# ESC_Tester_SCH.net
KiCad netlist of a schematic drawn in Altium Designer
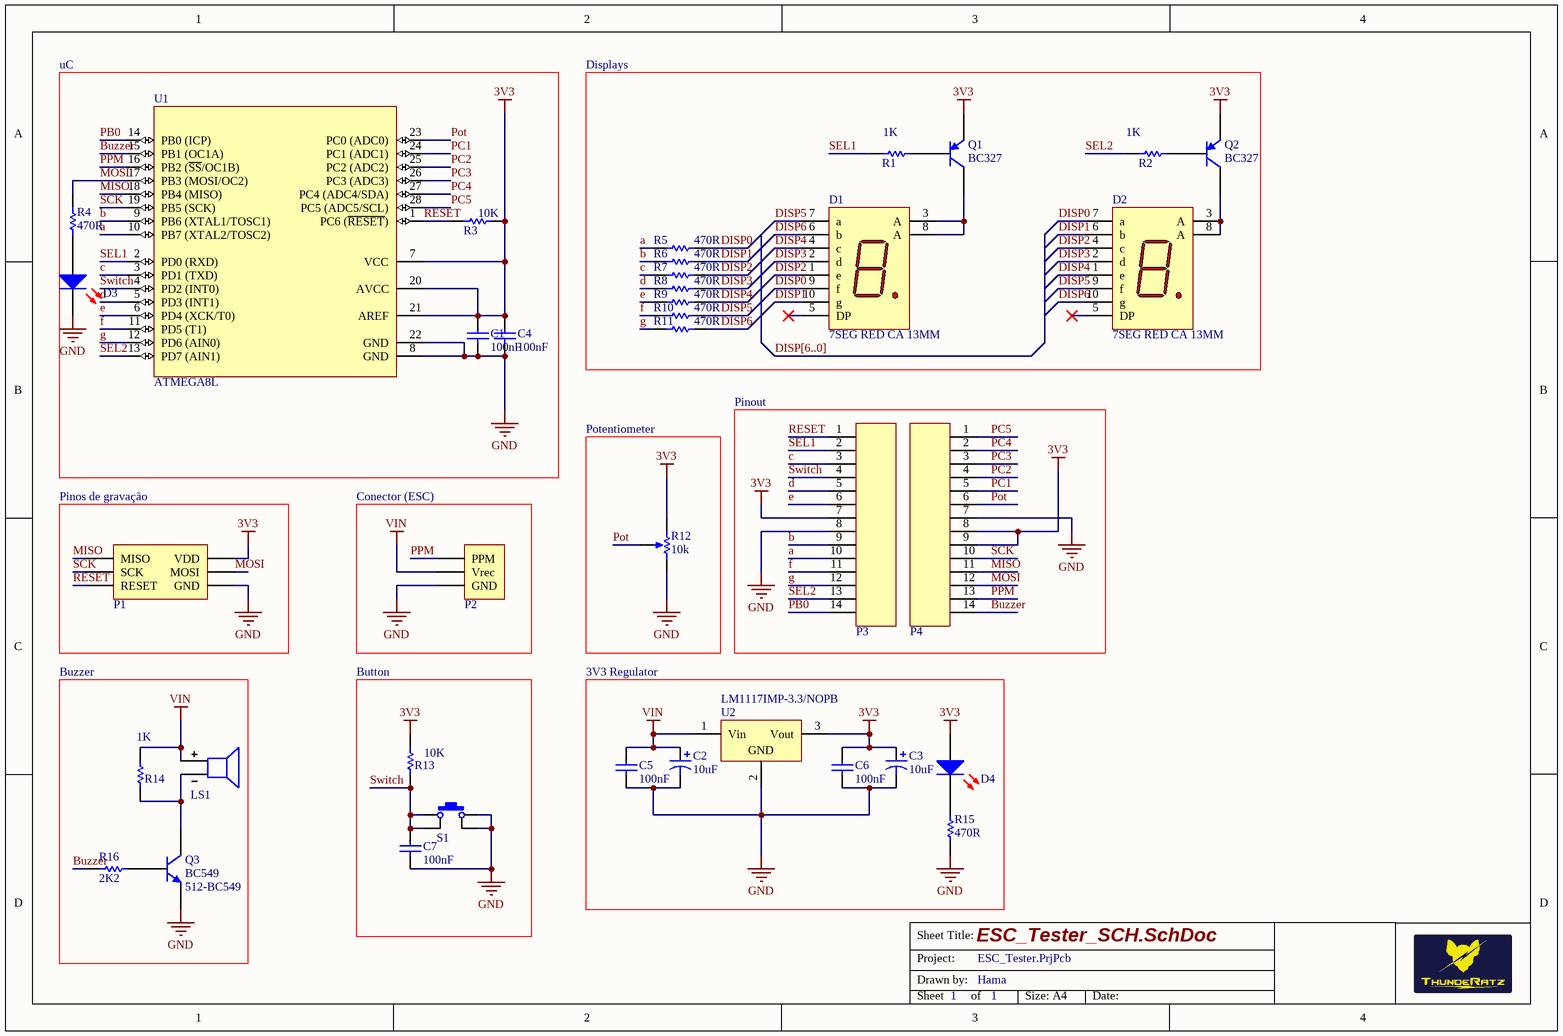
[diagram p0: ESC_Tester_SCH.SchDoc]

(export (version "E")
  (design (tool "Eeschema 10.0.6"))
  (components
    (comp (ref "C1")
      (value "Cap Film 0.1uF")
      (footprint "Cap Film 0.1uF")
      (description "Cap Film 0.1uF 63V PET 10% (7.2 X 2.5 X 6.5mm) Radial 5mm 125C Bulk")
      (fields
        (field (name "MANUFACTURER") "TDK EPCOS")
        (field (name "MANUFACTURER PART NUMBER") "B32529C104K")
        (field (name "CAPACITANCE") "100nF")
      )
      (libsource (lib "ESC_Tester_SCHLIB") (part "Cap Film 0.1uF - B32529C104K"))
    )
    (comp (ref "C2")
      (value "10uF")
      (footprint "CAP RAD 10UF 35V")
      (description "CAP ELE RAD 10uF 16V")
      (fields (field (name "MANUFACTURER PART NUMBER") "IMP1295"))
      (libsource (lib "ESC_Tester_SCHLIB") (part "CAP ELE RAD 10uF 16V"))
    )
    (comp (ref "C3")
      (value "10uF")
      (footprint "CAP RAD 10UF 35V")
      (description "CAP ELE RAD 10uF 16V")
      (fields (field (name "MANUFACTURER PART NUMBER") "IMP1295"))
      (libsource (lib "ESC_Tester_SCHLIB") (part "CAP ELE RAD 10uF 16V"))
    )
    (comp (ref "C4")
      (value "Cap Film 0.1uF")
      (footprint "Cap Film 0.1uF")
      (description "Cap Film 0.1uF 63V PET 10% (7.2 X 2.5 X 6.5mm) Radial 5mm 125C Bulk")
      (fields
        (field (name "MANUFACTURER") "TDK EPCOS")
        (field (name "MANUFACTURER PART NUMBER") "B32529C104K")
        (field (name "CAPACITANCE") "100nF")
      )
      (libsource (lib "ESC_Tester_SCHLIB") (part "Cap Film 0.1uF - B32529C104K"))
    )
    (comp (ref "C5")
      (value "Cap Film 0.1uF")
      (footprint "Cap Film 0.1uF")
      (description "Cap Film 0.1uF 63V PET 10% (7.2 X 2.5 X 6.5mm) Radial 5mm 125C Bulk")
      (fields
        (field (name "MANUFACTURER") "TDK EPCOS")
        (field (name "MANUFACTURER PART NUMBER") "B32529C104K")
        (field (name "CAPACITANCE") "100nF")
      )
      (libsource (lib "ESC_Tester_SCHLIB") (part "Cap Film 0.1uF - B32529C104K"))
    )
    (comp (ref "C6")
      (value "Cap Film 0.1uF")
      (footprint "Cap Film 0.1uF")
      (description "Cap Film 0.1uF 63V PET 10% (7.2 X 2.5 X 6.5mm) Radial 5mm 125C Bulk")
      (fields
        (field (name "MANUFACTURER") "TDK EPCOS")
        (field (name "MANUFACTURER PART NUMBER") "B32529C104K")
        (field (name "CAPACITANCE") "100nF")
      )
      (libsource (lib "ESC_Tester_SCHLIB") (part "Cap Film 0.1uF - B32529C104K"))
    )
    (comp (ref "C7")
      (value "Cap Film 0.1uF")
      (footprint "Cap Film 0.1uF")
      (description "Cap Film 0.1uF 63V PET 10% (7.2 X 2.5 X 6.5mm) Radial 5mm 125C Bulk")
      (fields
        (field (name "MANUFACTURER") "TDK EPCOS")
        (field (name "MANUFACTURER PART NUMBER") "B32529C104K")
        (field (name "CAPACITANCE") "100nF")
      )
      (libsource (lib "ESC_Tester_SCHLIB") (part "Cap Film 0.1uF - B32529C104K"))
    )
    (comp (ref "D1")
      (value "7SEG RED CA 13MM")
      (footprint "7SEG RED PTH")
      (description "PHOTONIC - PHDE113A - DISPLAY, SEVEN SEGMENT, 13MM, RED")
      (fields (field (name "MANUFACTURER") "Photonic") (field (name "MANUFACTURER PART NUMBER") "PHDE113A"))
      (libsource (lib "PS_LIB_SCH") (part "7SEG RED CA 13MM"))
    )
    (comp (ref "D2")
      (value "7SEG RED CA 13MM")
      (footprint "7SEG RED PTH")
      (description "PHOTONIC - PHDE113A - DISPLAY, SEVEN SEGMENT, 13MM, RED")
      (fields (field (name "MANUFACTURER") "Photonic") (field (name "MANUFACTURER PART NUMBER") "PHDE113A"))
      (libsource (lib "PS_LIB_SCH") (part "7SEG RED CA 13MM"))
    )
    (comp (ref "D3")
      (value "LED 5MM RED")
      (footprint "LED 5MM RED")
      (fields (field (name "MANUFACTURER") "Paralight") (field (name "MANUFACTURER PART NUMBER") "IMP585"))
      (libsource (lib "ESC_Tester_SCHLIB") (part "LED 5MM RED"))
    )
    (comp (ref "D4")
      (value "LED 5MM RED")
      (footprint "LED 5MM RED")
      (fields (field (name "MANUFACTURER") "Paralight") (field (name "MANUFACTURER PART NUMBER") "IMP585"))
      (libsource (lib "ESC_Tester_SCHLIB") (part "LED 5MM RED"))
    )
    (comp (ref "LS1")
      (value "Buzzer")
      (footprint "BUZZER 12x6MM")
      (description "AUDIO PIEZO TRANSDUCER 30V TH")
      (fields
        (field (name "MANUFACTURER") "TDK Corporation")
        (field (name "MANUFACTURER PART NUMBER") "PS1240P02BT")
      )
      (libsource (lib "ESC_Tester_SCHLIB") (part "AUDIO PIEZO TRANSDUCER 30V TH"))
    )
    (comp (ref "P1")
      (value "87758-4016")
      (footprint "HDR MALE 2x3")
      (description "Headers & Wire Housings VERT HEADER 40P Lead Free")
      (fields (field (name "MANUFACTURER") "Molex"))
      (libsource (lib "ESC_Tester_SCHLIB") (part "87758-4016"))
    )
    (comp (ref "P2")
      (value "920-0018-01")
      (footprint "HDR MALE 1x3")
      (description "Headers & Wire Housings 40Pin 2mm Spacing Single Row Hdrs, 5pc")
      (fields (field (name "MANUFACTURER") "SchmartBoard"))
      (libsource (lib "PS_LIB_SCH") (part "920-0018-01_1"))
    )
    (comp (ref "P3")
      (value "Header Female 1x14")
      (footprint "HDR FEMALE 1x14")
      (description "Headers & Wire Housings 40Pin 2mm Spacing Single Row Hdrs, 5pc")
      (fields (field (name "MANUFACTURER") "Cromax"))
      (libsource (lib "ESC_Tester_SCHLIB") (part "Header Female 1x14"))
    )
    (comp (ref "P4")
      (value "Header Female 1x14")
      (footprint "HDR FEMALE 1x14")
      (description "Headers & Wire Housings 40Pin 2mm Spacing Single Row Hdrs, 5pc")
      (fields (field (name "MANUFACTURER") "Cromax"))
      (libsource (lib "") (part "Header Female 1x14_1"))
    )
    (comp (ref "Q1")
      (value "BC327")
      (footprint "TO92")
      (description "Bipolar Transistors - BJT PNP -45V -800mA HFE/630")
      (fields (field (name "MANUFACTURER") "Fairchild Semiconductor"))
      (libsource (lib "PS_LIB_SCH") (part "BC327 BJT PNP TO92"))
    )
    (comp (ref "Q2")
      (value "BC327")
      (footprint "TO92")
      (description "Bipolar Transistors - BJT PNP -45V -800mA HFE/630")
      (fields (field (name "MANUFACTURER") "Fairchild Semiconductor"))
      (libsource (lib "PS_LIB_SCH") (part "BC327 BJT PNP TO92"))
    )
    (comp (ref "Q3")
      (value "BC549")
      (footprint "TO92")
      (description "TRANS NPN 30V 0.1A TO-92")
      (fields
        (field (name "MANUFACTURER") "Fairchild Semiconductor")
        (field (name "SUPPLIER PART NUMBER 1") "512-BC549")
      )
      (libsource (lib "PS_LIB_SCH") (part "BC549"))
    )
    (comp (ref "R1")
      (value "RES 1K 1/4W CARBON FILM")
      (footprint "RES 1K 1/4W CARBON FILM")
      (description "RES 1K OHM 1/4W 5% CARBON FILM")
      (fields
        (field (name "MANUFACTURER") "Ty-Ohm")
        (field (name "MANUFACTURER PART NUMBER") "CR25")
        (field (name "RESISTANCE (OHMS)") "1K")
      )
      (libsource (lib "PS_LIB_SCH") (part "RES 1K 1/4W CARBON FILM"))
    )
    (comp (ref "R2")
      (value "RES 1K 1/4W CARBON FILM")
      (footprint "RES 1K 1/4W CARBON FILM")
      (description "RES 1K OHM 1/4W 5% CARBON FILM")
      (fields
        (field (name "MANUFACTURER") "Ty-Ohm")
        (field (name "MANUFACTURER PART NUMBER") "CR25")
        (field (name "RESISTANCE (OHMS)") "1K")
      )
      (libsource (lib "PS_LIB_SCH") (part "RES 1K 1/4W CARBON FILM"))
    )
    (comp (ref "R3")
      (value "RES 10K 1/4W CARBON FILM")
      (footprint "RES 10K 1/4W CARBON FILM")
      (description "RES 10K OHM 1/4W 5% CARBON FILM")
      (fields
        (field (name "MANUFACTURER") "Ty-Ohm")
        (field (name "MANUFACTURER PART NUMBER") "CR25")
        (field (name "RESISTANCE (OHMS)") "10K")
      )
      (libsource (lib "ESC_Tester_SCHLIB") (part "RES 10K 1/4W CARBON FILM"))
    )
    (comp (ref "R4")
      (value "RES 470R 1/4W CARBON FILM")
      (footprint "RES 470R 1/4W CARBON FILM_STAND")
      (description "RES 470R OHM 1/4W 5% CARBON FILM")
      (fields
        (field (name "MANUFACTURER") "Ty-Ohm")
        (field (name "MANUFACTURER PART NUMBER") "CR25")
        (field (name "RESISTANCE (OHMS)") "470R")
      )
      (libsource (lib "ESC_Tester_SCHLIB") (part "RES 470R 1/4W CARBON FILM"))
    )
    (comp (ref "R5")
      (value "RES 470R 1/4W CARBON FILM")
      (footprint "RES 470R 1/4W CARBON FILM")
      (description "RES 470R OHM 1/4W 5% CARBON FILM")
      (fields
        (field (name "MANUFACTURER") "Ty-Ohm")
        (field (name "MANUFACTURER PART NUMBER") "CR25")
        (field (name "RESISTANCE (OHMS)") "470R")
      )
      (libsource (lib "PS_LIB_SCH") (part "RES 470R 1/4W CARBON FILM"))
    )
    (comp (ref "R6")
      (value "RES 470R 1/4W CARBON FILM")
      (footprint "RES 470R 1/4W CARBON FILM")
      (description "RES 470R OHM 1/4W 5% CARBON FILM")
      (fields
        (field (name "MANUFACTURER") "Ty-Ohm")
        (field (name "MANUFACTURER PART NUMBER") "CR25")
        (field (name "RESISTANCE (OHMS)") "470R")
      )
      (libsource (lib "PS_LIB_SCH") (part "RES 470R 1/4W CARBON FILM"))
    )
    (comp (ref "R7")
      (value "RES 470R 1/4W CARBON FILM")
      (footprint "RES 470R 1/4W CARBON FILM")
      (description "RES 470R OHM 1/4W 5% CARBON FILM")
      (fields
        (field (name "MANUFACTURER") "Ty-Ohm")
        (field (name "MANUFACTURER PART NUMBER") "CR25")
        (field (name "RESISTANCE (OHMS)") "470R")
      )
      (libsource (lib "PS_LIB_SCH") (part "RES 470R 1/4W CARBON FILM"))
    )
    (comp (ref "R8")
      (value "RES 470R 1/4W CARBON FILM")
      (footprint "RES 470R 1/4W CARBON FILM")
      (description "RES 470R OHM 1/4W 5% CARBON FILM")
      (fields
        (field (name "MANUFACTURER") "Ty-Ohm")
        (field (name "MANUFACTURER PART NUMBER") "CR25")
        (field (name "RESISTANCE (OHMS)") "470R")
      )
      (libsource (lib "PS_LIB_SCH") (part "RES 470R 1/4W CARBON FILM"))
    )
    (comp (ref "R9")
      (value "RES 470R 1/4W CARBON FILM")
      (footprint "RES 470R 1/4W CARBON FILM")
      (description "RES 470R OHM 1/4W 5% CARBON FILM")
      (fields
        (field (name "MANUFACTURER") "Ty-Ohm")
        (field (name "MANUFACTURER PART NUMBER") "CR25")
        (field (name "RESISTANCE (OHMS)") "470R")
      )
      (libsource (lib "PS_LIB_SCH") (part "RES 470R 1/4W CARBON FILM"))
    )
    (comp (ref "R10")
      (value "RES 470R 1/4W CARBON FILM")
      (footprint "RES 470R 1/4W CARBON FILM")
      (description "RES 470R OHM 1/4W 5% CARBON FILM")
      (fields
        (field (name "MANUFACTURER") "Ty-Ohm")
        (field (name "MANUFACTURER PART NUMBER") "CR25")
        (field (name "RESISTANCE (OHMS)") "470R")
      )
      (libsource (lib "PS_LIB_SCH") (part "RES 470R 1/4W CARBON FILM"))
    )
    (comp (ref "R11")
      (value "RES 470R 1/4W CARBON FILM")
      (footprint "RES 470R 1/4W CARBON FILM")
      (description "RES 470R OHM 1/4W 5% CARBON FILM")
      (fields
        (field (name "MANUFACTURER") "Ty-Ohm")
        (field (name "MANUFACTURER PART NUMBER") "CR25")
        (field (name "RESISTANCE (OHMS)") "470R")
      )
      (libsource (lib "PS_LIB_SCH") (part "RES 470R 1/4W CARBON FILM"))
    )
    (comp (ref "R12")
      (value "Pot 10k")
      (footprint "Pot 10k")
      (description "POT 10K OHM 1/20W PLASTIC LINEAR")
      (fields
        (field (name "MANUFACTURER") "TT Electronics/BI")
        (field (name "MANUFACTURER PART NUMBER") "P120PK-Y25BR10K")
        (field (name "RESISTANCE (OHMS)") "10k")
      )
      (libsource (lib "PS_LIB_SCH") (part "Pot 10k"))
    )
    (comp (ref "R13")
      (value "RES 10K 1/4W CARBON FILM")
      (footprint "RES 10K 1/4W CARBON FILM")
      (description "RES 10K OHM 1/4W 5% CARBON FILM")
      (fields
        (field (name "MANUFACTURER") "Ty-Ohm")
        (field (name "MANUFACTURER PART NUMBER") "CR25")
        (field (name "RESISTANCE (OHMS)") "10K")
      )
      (libsource (lib "PS_LIB_SCH") (part "RES 10K 1/4W CARBON FILM"))
    )
    (comp (ref "R14")
      (value "RES 1K 1/4W CARBON FILM")
      (footprint "RES 1K 1/4W CARBON FILM")
      (description "RES 1K OHM 1/4W 5% CARBON FILM")
      (fields
        (field (name "MANUFACTURER") "Ty-Ohm")
        (field (name "MANUFACTURER PART NUMBER") "CR25")
        (field (name "RESISTANCE (OHMS)") "1K")
      )
      (libsource (lib "PS_LIB_SCH") (part "RES 1K 1/4W CARBON FILM"))
    )
    (comp (ref "R15")
      (value "RES 470R 1/4W CARBON FILM")
      (footprint "RES 470R 1/4W CARBON FILM_STAND")
      (description "RES 470R OHM 1/4W 5% CARBON FILM")
      (fields
        (field (name "MANUFACTURER") "Ty-Ohm")
        (field (name "MANUFACTURER PART NUMBER") "CR25")
        (field (name "RESISTANCE (OHMS)") "470R")
      )
      (libsource (lib "ESC_Tester_SCHLIB") (part "RES 470R 1/4W CARBON FILM"))
    )
    (comp (ref "R16")
      (value "RES 2K2 1/4W CARBON FILM")
      (footprint "RES 2K2 1/4W CARBON FILM")
      (description "RES 2K2 OHM 1/4W 5% CARBON FILM")
      (fields
        (field (name "MANUFACTURER") "Ty-Ohm")
        (field (name "MANUFACTURER PART NUMBER") "CR25")
        (field (name "RESISTANCE (OHMS)") "2K2")
      )
      (libsource (lib "ESC_Tester_SCHLIB") (part "RES 2K2 1/4W CARBON FILM"))
    )
    (comp (ref "S1")
      (value "SPST-NO")
      (footprint "TACT SWITCH 6X6X7MM")
      (description "SWITCH TACTILE SPST-NO 0.02A 15V")
      (fields
        (field (name "MANUFACTURER") "Panasonic Electronic Components")
        (field (name "MANUFACTURER PART NUMBER") "EVQ-PAC07K")
      )
      (libsource (lib "PS_LIB_SCH") (part "SWITCH TACTILE SPST-NO 0.02A 15V"))
    )
    (comp (ref "U1")
      (value "ATMEGA8L")
      (footprint "DIP28")
      (description "8-bit Microcontrollers - MCU 8kB Flash 0.5kB EEPROM 23 I/O Pins")
      (fields (field (name "MANUFACTURER") "Atmel") (field (name "MANUFACTURER PART NUMBER") "ATmega8L-8PU"))
      (libsource (lib "PS_LIB_SCH") (part "MCU ATMEGA8L-8PU PDIP28_1"))
    )
    (comp (ref "U2")
      (value "LM1117IMP-3.3/NOPB")
      (footprint "TO220AB")
      (description "TEXAS INSTRUMENTS   LM1117IMP-3.3/NOPB   LDO, 1.2VDO, 3.3V, 1%, 0.8A, 3SOT223")
      (fields (field (name "MANUFACTURER") "Texas Instruments"))
      (libsource (lib "ESC_Tester_SCHLIB") (part "LM1117IMP-3.3/NOPB"))
    )
  )
  (nets
    (net (code "1") (name "/Buzzer") (class "Default")
      (node (ref "P4") (pin "14") (pintype "passive"))
      (node (ref "R16") (pin "1") (pinfunction "1_1") (pintype "passive"))
      (node (ref "U1") (pin "15") (pinfunction "PB1_(OC1A)_15") (pintype "bidirectional"))
    )
    (net (code "2") (name "/DISP0") (class "Default")
      (node (ref "D1") (pin "9") (pinfunction "f_9") (pintype "passive"))
      (node (ref "D2") (pin "7") (pinfunction "a_7") (pintype "passive"))
      (node (ref "R5") (pin "2") (pinfunction "2_2") (pintype "passive"))
    )
    (net (code "3") (name "/DISP1") (class "Default")
      (node (ref "D1") (pin "10") (pinfunction "g_10") (pintype "passive"))
      (node (ref "D2") (pin "6") (pinfunction "b_6") (pintype "passive"))
      (node (ref "R6") (pin "2") (pinfunction "2_2") (pintype "passive"))
    )
    (net (code "4") (name "/DISP2") (class "Default")
      (node (ref "D1") (pin "1") (pinfunction "e_1") (pintype "passive"))
      (node (ref "D2") (pin "4") (pinfunction "c_4") (pintype "passive"))
      (node (ref "R7") (pin "2") (pinfunction "2_2") (pintype "passive"))
    )
    (net (code "5") (name "/DISP3") (class "Default")
      (node (ref "D1") (pin "2") (pinfunction "d_2") (pintype "passive"))
      (node (ref "D2") (pin "2") (pinfunction "d_2") (pintype "passive"))
      (node (ref "R8") (pin "2") (pinfunction "2_2") (pintype "passive"))
    )
    (net (code "6") (name "/DISP4") (class "Default")
      (node (ref "D1") (pin "4") (pinfunction "c_4") (pintype "passive"))
      (node (ref "D2") (pin "1") (pinfunction "e_1") (pintype "passive"))
      (node (ref "R9") (pin "2") (pinfunction "2_2") (pintype "passive"))
    )
    (net (code "7") (name "/DISP5") (class "Default")
      (node (ref "D1") (pin "7") (pinfunction "a_7") (pintype "passive"))
      (node (ref "D2") (pin "9") (pinfunction "f_9") (pintype "passive"))
      (node (ref "R10") (pin "2") (pinfunction "2_2") (pintype "passive"))
    )
    (net (code "8") (name "/DISP6") (class "Default")
      (node (ref "D1") (pin "6") (pinfunction "b_6") (pintype "passive"))
      (node (ref "D2") (pin "10") (pinfunction "g_10") (pintype "passive"))
      (node (ref "R11") (pin "2") (pinfunction "2_2") (pintype "passive"))
    )
    (net (code "10") (name "/MISO") (class "Default")
      (node (ref "P1") (pin "6") (pinfunction "MISO_6") (pintype "passive"))
      (node (ref "P4") (pin "11") (pintype "passive"))
      (node (ref "U1") (pin "18") (pinfunction "PB4_(MISO)_18") (pintype "bidirectional"))
    )
    (net (code "11") (name "/MOSI") (class "Default")
      (node (ref "P1") (pin "3") (pinfunction "MOSI_3") (pintype "passive"))
      (node (ref "P4") (pin "12") (pintype "passive"))
      (node (ref "R4") (pin "2") (pinfunction "2_2") (pintype "passive"))
      (node (ref "U1") (pin "17") (pinfunction "PB3_(MOSI/OC2)_17") (pintype "bidirectional"))
    )
    (net (code "12") (name "/PB0") (class "Default")
      (node (ref "P3") (pin "14") (pintype "passive"))
      (node (ref "U1") (pin "14") (pinfunction "PB0_(ICP)_14") (pintype "bidirectional"))
    )
    (net (code "13") (name "/PC1") (class "Default")
      (node (ref "P4") (pin "5") (pintype "passive"))
      (node (ref "U1") (pin "24") (pinfunction "PC1_(ADC1)_24") (pintype "bidirectional"))
    )
    (net (code "14") (name "/PC2") (class "Default")
      (node (ref "P4") (pin "4") (pintype "passive"))
      (node (ref "U1") (pin "25") (pinfunction "PC2_(ADC2)_25") (pintype "bidirectional"))
    )
    (net (code "15") (name "/PC3") (class "Default")
      (node (ref "P4") (pin "3") (pintype "passive"))
      (node (ref "U1") (pin "26") (pinfunction "PC3_(ADC3)_26") (pintype "bidirectional"))
    )
    (net (code "16") (name "/PC4") (class "Default")
      (node (ref "P4") (pin "2") (pintype "passive"))
      (node (ref "U1") (pin "27") (pinfunction "PC4_(ADC4/SDA)_27") (pintype "bidirectional"))
    )
    (net (code "17") (name "/PC5") (class "Default")
      (node (ref "P4") (pin "1") (pintype "passive"))
      (node (ref "U1") (pin "28") (pinfunction "PC5_(ADC5/SCL)_28") (pintype "bidirectional"))
    )
    (net (code "18") (name "/PPM") (class "Default")
      (node (ref "P2") (pin "1") (pinfunction "PPM_1") (pintype "passive"))
      (node (ref "P4") (pin "13") (pintype "passive"))
      (node (ref "U1") (pin "16") (pinfunction "PB2_(~{SS}/OC1B)_16") (pintype "bidirectional"))
    )
    (net (code "19") (name "/Pot") (class "Default")
      (node (ref "P4") (pin "6") (pintype "passive"))
      (node (ref "R12") (pin "2") (pinfunction "TAP_2") (pintype "passive"))
      (node (ref "U1") (pin "23") (pinfunction "PC0_(ADC0)_23") (pintype "bidirectional"))
    )
    (net (code "20") (name "/RESET") (class "Default")
      (node (ref "P1") (pin "2") (pinfunction "RESET_2") (pintype "passive"))
      (node (ref "P3") (pin "1") (pintype "passive"))
      (node (ref "R3") (pin "1") (pinfunction "1_1") (pintype "passive"))
      (node (ref "U1") (pin "1") (pinfunction "PC6_(~{RESET})_1") (pintype "bidirectional"))
    )
    (net (code "21") (name "/SCK") (class "Default")
      (node (ref "P1") (pin "4") (pinfunction "SCK_4") (pintype "passive"))
      (node (ref "P4") (pin "10") (pintype "passive"))
      (node (ref "U1") (pin "19") (pinfunction "PB5_(SCK)_19") (pintype "bidirectional"))
    )
    (net (code "22") (name "/SEL1") (class "Default")
      (node (ref "P3") (pin "2") (pintype "passive"))
      (node (ref "R1") (pin "1") (pinfunction "1_1") (pintype "passive"))
      (node (ref "U1") (pin "2") (pinfunction "PD0_(RXD)_2") (pintype "bidirectional"))
    )
    (net (code "23") (name "/SEL2") (class "Default")
      (node (ref "P3") (pin "13") (pintype "passive"))
      (node (ref "R2") (pin "1") (pinfunction "1_1") (pintype "passive"))
      (node (ref "U1") (pin "13") (pinfunction "PD7_(AIN1)_13") (pintype "bidirectional"))
    )
    (net (code "24") (name "/Switch") (class "Default")
      (node (ref "C7") (pin "2") (pinfunction "2_2") (pintype "passive"))
      (node (ref "P3") (pin "4") (pintype "passive"))
      (node (ref "R13") (pin "1") (pinfunction "1_1") (pintype "passive"))
      (node (ref "S1") (pin "1") (pinfunction "1_1") (pintype "passive"))
      (node (ref "S1") (pin "2") (pinfunction "2_2") (pintype "passive"))
      (node (ref "U1") (pin "4") (pinfunction "PD2_(INT0)_4") (pintype "bidirectional"))
    )
    (net (code "25") (name "/a") (class "Default")
      (node (ref "P3") (pin "10") (pintype "passive"))
      (node (ref "R5") (pin "1") (pinfunction "1_1") (pintype "passive"))
      (node (ref "U1") (pin "10") (pinfunction "PB7_(XTAL2/TOSC2)_10") (pintype "bidirectional"))
    )
    (net (code "26") (name "/b") (class "Default")
      (node (ref "P3") (pin "9") (pintype "passive"))
      (node (ref "R6") (pin "1") (pinfunction "1_1") (pintype "passive"))
      (node (ref "U1") (pin "9") (pinfunction "PB6_(XTAL1/TOSC1)_9") (pintype "bidirectional"))
    )
    (net (code "27") (name "/c") (class "Default")
      (node (ref "P3") (pin "3") (pintype "passive"))
      (node (ref "R7") (pin "1") (pinfunction "1_1") (pintype "passive"))
      (node (ref "U1") (pin "3") (pinfunction "PD1_(TXD)_3") (pintype "bidirectional"))
    )
    (net (code "28") (name "/d") (class "Default")
      (node (ref "P3") (pin "5") (pintype "passive"))
      (node (ref "R8") (pin "1") (pinfunction "1_1") (pintype "passive"))
      (node (ref "U1") (pin "5") (pinfunction "PD3_(INT1)_5") (pintype "bidirectional"))
    )
    (net (code "29") (name "/e") (class "Default")
      (node (ref "P3") (pin "6") (pintype "passive"))
      (node (ref "R9") (pin "1") (pinfunction "1_1") (pintype "passive"))
      (node (ref "U1") (pin "6") (pinfunction "PD4_(XCK/T0)_6") (pintype "bidirectional"))
    )
    (net (code "30") (name "/f") (class "Default")
      (node (ref "P3") (pin "11") (pintype "passive"))
      (node (ref "R10") (pin "1") (pinfunction "1_1") (pintype "passive"))
      (node (ref "U1") (pin "11") (pinfunction "PD5_(T1)_11") (pintype "bidirectional"))
    )
    (net (code "31") (name "/g") (class "Default")
      (node (ref "P3") (pin "12") (pintype "passive"))
      (node (ref "R11") (pin "1") (pinfunction "1_1") (pintype "passive"))
      (node (ref "U1") (pin "12") (pinfunction "PD6_(AIN0)_12") (pintype "bidirectional"))
    )
    (net (code "32") (name "3V3") (class "Default")
      (node (ref "C1") (pin "2") (pinfunction "2_2") (pintype "passive"))
      (node (ref "C3") (pin "1") (pinfunction "1_1") (pintype "passive"))
      (node (ref "C4") (pin "2") (pinfunction "2_2") (pintype "passive"))
      (node (ref "C6") (pin "2") (pinfunction "2_2") (pintype "passive"))
      (node (ref "D4") (pin "1") (pinfunction "A_1") (pintype "passive"))
      (node (ref "P1") (pin "5") (pinfunction "VDD_5") (pintype "power_in"))
      (node (ref "P3") (pin "7") (pintype "passive"))
      (node (ref "P4") (pin "8") (pintype "passive"))
      (node (ref "P4") (pin "9") (pintype "passive"))
      (node (ref "Q1") (pin "3") (pinfunction "E_3") (pintype "passive"))
      (node (ref "Q2") (pin "3") (pinfunction "E_3") (pintype "passive"))
      (node (ref "R12") (pin "3") (pinfunction "BOT_3") (pintype "passive"))
      (node (ref "R13") (pin "2") (pinfunction "2_2") (pintype "passive"))
      (node (ref "R3") (pin "2") (pinfunction "2_2") (pintype "passive"))
      (node (ref "U1") (pin "20") (pinfunction "AVCC_20") (pintype "power_in"))
      (node (ref "U1") (pin "21") (pinfunction "AREF_21") (pintype "passive"))
      (node (ref "U1") (pin "7") (pinfunction "VCC_7") (pintype "power_in"))
      (node (ref "U2") (pin "3") (pinfunction "Vout_3") (pintype "passive"))
    )
    (net (code "33") (name "GND") (class "Default")
      (node (ref "C1") (pin "1") (pinfunction "1_1") (pintype "passive"))
      (node (ref "C2") (pin "2") (pinfunction "2_2") (pintype "passive"))
      (node (ref "C3") (pin "2") (pinfunction "2_2") (pintype "passive"))
      (node (ref "C4") (pin "1") (pinfunction "1_1") (pintype "passive"))
      (node (ref "C5") (pin "1") (pinfunction "1_1") (pintype "passive"))
      (node (ref "C6") (pin "1") (pinfunction "1_1") (pintype "passive"))
      (node (ref "C7") (pin "1") (pinfunction "1_1") (pintype "passive"))
      (node (ref "D3") (pin "2") (pinfunction "K_2") (pintype "passive"))
      (node (ref "P1") (pin "1") (pinfunction "GND_1") (pintype "power_in"))
      (node (ref "P2") (pin "3") (pinfunction "GND_3") (pintype "power_in"))
      (node (ref "P3") (pin "8") (pintype "passive"))
      (node (ref "P4") (pin "7") (pintype "passive"))
      (node (ref "Q3") (pin "3") (pinfunction "E_3") (pintype "passive"))
      (node (ref "R12") (pin "1") (pinfunction "TOP_1") (pintype "passive"))
      (node (ref "R15") (pin "2") (pinfunction "2_2") (pintype "passive"))
      (node (ref "S1") (pin "3") (pinfunction "3_3") (pintype "passive"))
      (node (ref "S1") (pin "4") (pinfunction "4_4") (pintype "passive"))
      (node (ref "U1") (pin "22") (pinfunction "GND_22") (pintype "power_in"))
      (node (ref "U1") (pin "8") (pinfunction "GND_8") (pintype "power_in"))
      (node (ref "U2") (pin "2") (pinfunction "GND_2") (pintype "passive"))
    )
    (net (code "34") (name "Net-(D3-A)") (class "Default")
      (node (ref "D3") (pin "1") (pinfunction "A_1") (pintype "passive"))
      (node (ref "R4") (pin "1") (pinfunction "1_1") (pintype "passive"))
    )
    (net (code "35") (name "Net-(D4-K)") (class "Default")
      (node (ref "D4") (pin "2") (pinfunction "K_2") (pintype "passive"))
      (node (ref "R15") (pin "1") (pinfunction "1_1") (pintype "passive"))
    )
    (net (code "36") (name "Net-(Q1-B)") (class "Default")
      (node (ref "Q1") (pin "2") (pinfunction "B_2") (pintype "passive"))
      (node (ref "R1") (pin "2") (pinfunction "2_2") (pintype "passive"))
    )
    (net (code "37") (name "Net-(Q1-C)") (class "Default")
      (node (ref "D1") (pin "3") (pinfunction "A_3") (pintype "passive"))
      (node (ref "D1") (pin "8") (pinfunction "A_8") (pintype "passive"))
      (node (ref "Q1") (pin "1") (pinfunction "C_1") (pintype "passive"))
    )
    (net (code "38") (name "Net-(Q2-B)") (class "Default")
      (node (ref "Q2") (pin "2") (pinfunction "B_2") (pintype "passive"))
      (node (ref "R2") (pin "2") (pinfunction "2_2") (pintype "passive"))
    )
    (net (code "39") (name "Net-(Q2-C)") (class "Default")
      (node (ref "D2") (pin "3") (pinfunction "A_3") (pintype "passive"))
      (node (ref "D2") (pin "8") (pinfunction "A_8") (pintype "passive"))
      (node (ref "Q2") (pin "1") (pinfunction "C_1") (pintype "passive"))
    )
    (net (code "40") (name "Net-(Q3-B)") (class "Default")
      (node (ref "Q3") (pin "2") (pinfunction "B_2") (pintype "passive"))
      (node (ref "R16") (pin "2") (pinfunction "2_2") (pintype "passive"))
    )
    (net (code "41") (name "Net-(Q3-C)") (class "Default")
      (node (ref "LS1") (pin "2") (pinfunction "2_2") (pintype "passive"))
      (node (ref "Q3") (pin "1") (pinfunction "C_1") (pintype "passive"))
      (node (ref "R14") (pin "1") (pinfunction "1_1") (pintype "passive"))
    )
    (net (code "42") (name "VIN") (class "Default")
      (node (ref "C2") (pin "1") (pinfunction "1_1") (pintype "passive"))
      (node (ref "C5") (pin "2") (pinfunction "2_2") (pintype "passive"))
      (node (ref "LS1") (pin "1") (pinfunction "1_1") (pintype "passive"))
      (node (ref "P2") (pin "2") (pinfunction "Vrec_2") (pintype "power_in"))
      (node (ref "R14") (pin "2") (pinfunction "2_2") (pintype "passive"))
      (node (ref "U2") (pin "1") (pinfunction "Vin_1") (pintype "passive"))
    )
    (net (code "43") (name "unconnected-(D1-DP-Pad5)") (class "Default")
      (node (ref "D1") (pin "5") (pinfunction "DP_5") (pintype "passive+no_connect"))
    )
    (net (code "44") (name "unconnected-(D2-DP-Pad5)") (class "Default")
      (node (ref "D2") (pin "5") (pinfunction "DP_5") (pintype "passive+no_connect"))
    )
  )
)
